# relay_board.net
KiCad netlist of a schematic drawn in EAGLE
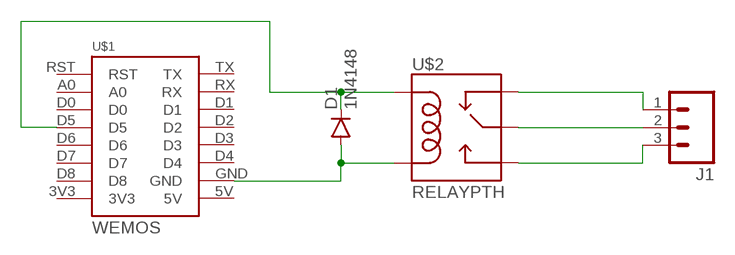
[diagram p0: schematic, sheet 1]

(export (version "E")
  (design (tool "Eeschema 10.0.6"))
  (components
    (comp (ref "D1")
      (value "1N4148")
      (footprint "eagle-import:DIODE-1N4148")
      (libsource (lib "eagle-import") (part "DIODE1N4148"))
    )
    (comp (ref "J1")
      (value "M03SCREW")
      (footprint "eagle-import:SCREWTERMINAL-3.5MM-3")
      (libsource (lib "eagle-import") (part "M03SCREW"))
    )
    (comp (ref "U$1")
      (value "WEMOS")
      (footprint "eagle-import:WEMOS")
      (libsource (lib "eagle-import") (part "WEMOS"))
    )
    (comp (ref "U$2")
      (value "RELAYPTH")
      (footprint "eagle-import:RELAY-G5Q")
      (libsource (lib "eagle-import") (part "RELAYPTH"))
    )
  )
  (nets
    (net (code "1") (name "Net-(U$2-COIL1)") (class "Default")
      (node (ref "D1") (pin "C") (pinfunction "C_C") (pintype "passive"))
      (node (ref "U$1") (pin "D5") (pinfunction "D5_D5") (pintype "bidirectional"))
      (node (ref "U$2") (pin "5") (pinfunction "COIL1_5") (pintype "bidirectional"))
    )
    (net (code "2") (name "Net-(U$2-COIL2)") (class "Default")
      (node (ref "D1") (pin "A") (pinfunction "A_A") (pintype "passive"))
      (node (ref "U$1") (pin "GND") (pinfunction "GND_GND") (pintype "bidirectional"))
      (node (ref "U$2") (pin "1") (pinfunction "COIL2_1") (pintype "bidirectional"))
    )
    (net (code "3") (name "Net-(U$2-MAIN)") (class "Default")
      (node (ref "J1") (pin "2") (pinfunction "2_2") (pintype "passive"))
      (node (ref "U$2") (pin "2") (pinfunction "MAIN_2") (pintype "bidirectional"))
    )
    (net (code "4") (name "Net-(U$2-NC)") (class "Default")
      (node (ref "J1") (pin "1") (pinfunction "1_1") (pintype "passive"))
      (node (ref "U$2") (pin "4") (pinfunction "NC_4") (pintype "bidirectional"))
    )
    (net (code "5") (name "Net-(U$2-NO)") (class "Default")
      (node (ref "J1") (pin "3") (pinfunction "3_3") (pintype "passive"))
      (node (ref "U$2") (pin "3") (pinfunction "NO_3") (pintype "bidirectional"))
    )
    (net (code "6") (name "unconnected-(U$1-Pad3V3)") (class "Default")
      (node (ref "U$1") (pin "3V3") (pinfunction "3V3_3V3") (pintype "bidirectional"))
    )
    (net (code "7") (name "unconnected-(U$1-Pad5V)") (class "Default")
      (node (ref "U$1") (pin "5V") (pinfunction "5V_5V") (pintype "bidirectional"))
    )
    (net (code "8") (name "unconnected-(U$1-PadA0)") (class "Default")
      (node (ref "U$1") (pin "A0") (pinfunction "A0_A0") (pintype "bidirectional"))
    )
    (net (code "9") (name "unconnected-(U$1-PadD0)") (class "Default")
      (node (ref "U$1") (pin "D0") (pinfunction "D0_D0") (pintype "bidirectional"))
    )
    (net (code "10") (name "unconnected-(U$1-PadD1)") (class "Default")
      (node (ref "U$1") (pin "D1") (pinfunction "D1_D1") (pintype "bidirectional"))
    )
    (net (code "11") (name "unconnected-(U$1-PadD2)") (class "Default")
      (node (ref "U$1") (pin "D2") (pinfunction "D2_D2") (pintype "bidirectional"))
    )
    (net (code "12") (name "unconnected-(U$1-PadD3)") (class "Default")
      (node (ref "U$1") (pin "D3") (pinfunction "D3_D3") (pintype "bidirectional"))
    )
    (net (code "13") (name "unconnected-(U$1-PadD4)") (class "Default")
      (node (ref "U$1") (pin "D4") (pinfunction "D4_D4") (pintype "bidirectional"))
    )
    (net (code "14") (name "unconnected-(U$1-PadD6)") (class "Default")
      (node (ref "U$1") (pin "D6") (pinfunction "D6_D6") (pintype "bidirectional"))
    )
    (net (code "15") (name "unconnected-(U$1-PadD7)") (class "Default")
      (node (ref "U$1") (pin "D7") (pinfunction "D7_D7") (pintype "bidirectional"))
    )
    (net (code "16") (name "unconnected-(U$1-PadD8)") (class "Default")
      (node (ref "U$1") (pin "D8") (pinfunction "D8_D8") (pintype "bidirectional"))
    )
    (net (code "17") (name "unconnected-(U$1-PadRST)") (class "Default")
      (node (ref "U$1") (pin "RST") (pinfunction "RST_RST") (pintype "bidirectional"))
    )
    (net (code "18") (name "unconnected-(U$1-PadRX)") (class "Default")
      (node (ref "U$1") (pin "RX") (pinfunction "RX_RX") (pintype "bidirectional"))
    )
    (net (code "19") (name "unconnected-(U$1-PadTX)") (class "Default")
      (node (ref "U$1") (pin "TX") (pinfunction "TX_TX") (pintype "bidirectional"))
    )
  )
)
